# MetaSenseV02_2.net
KiCad netlist of a schematic drawn in EAGLE
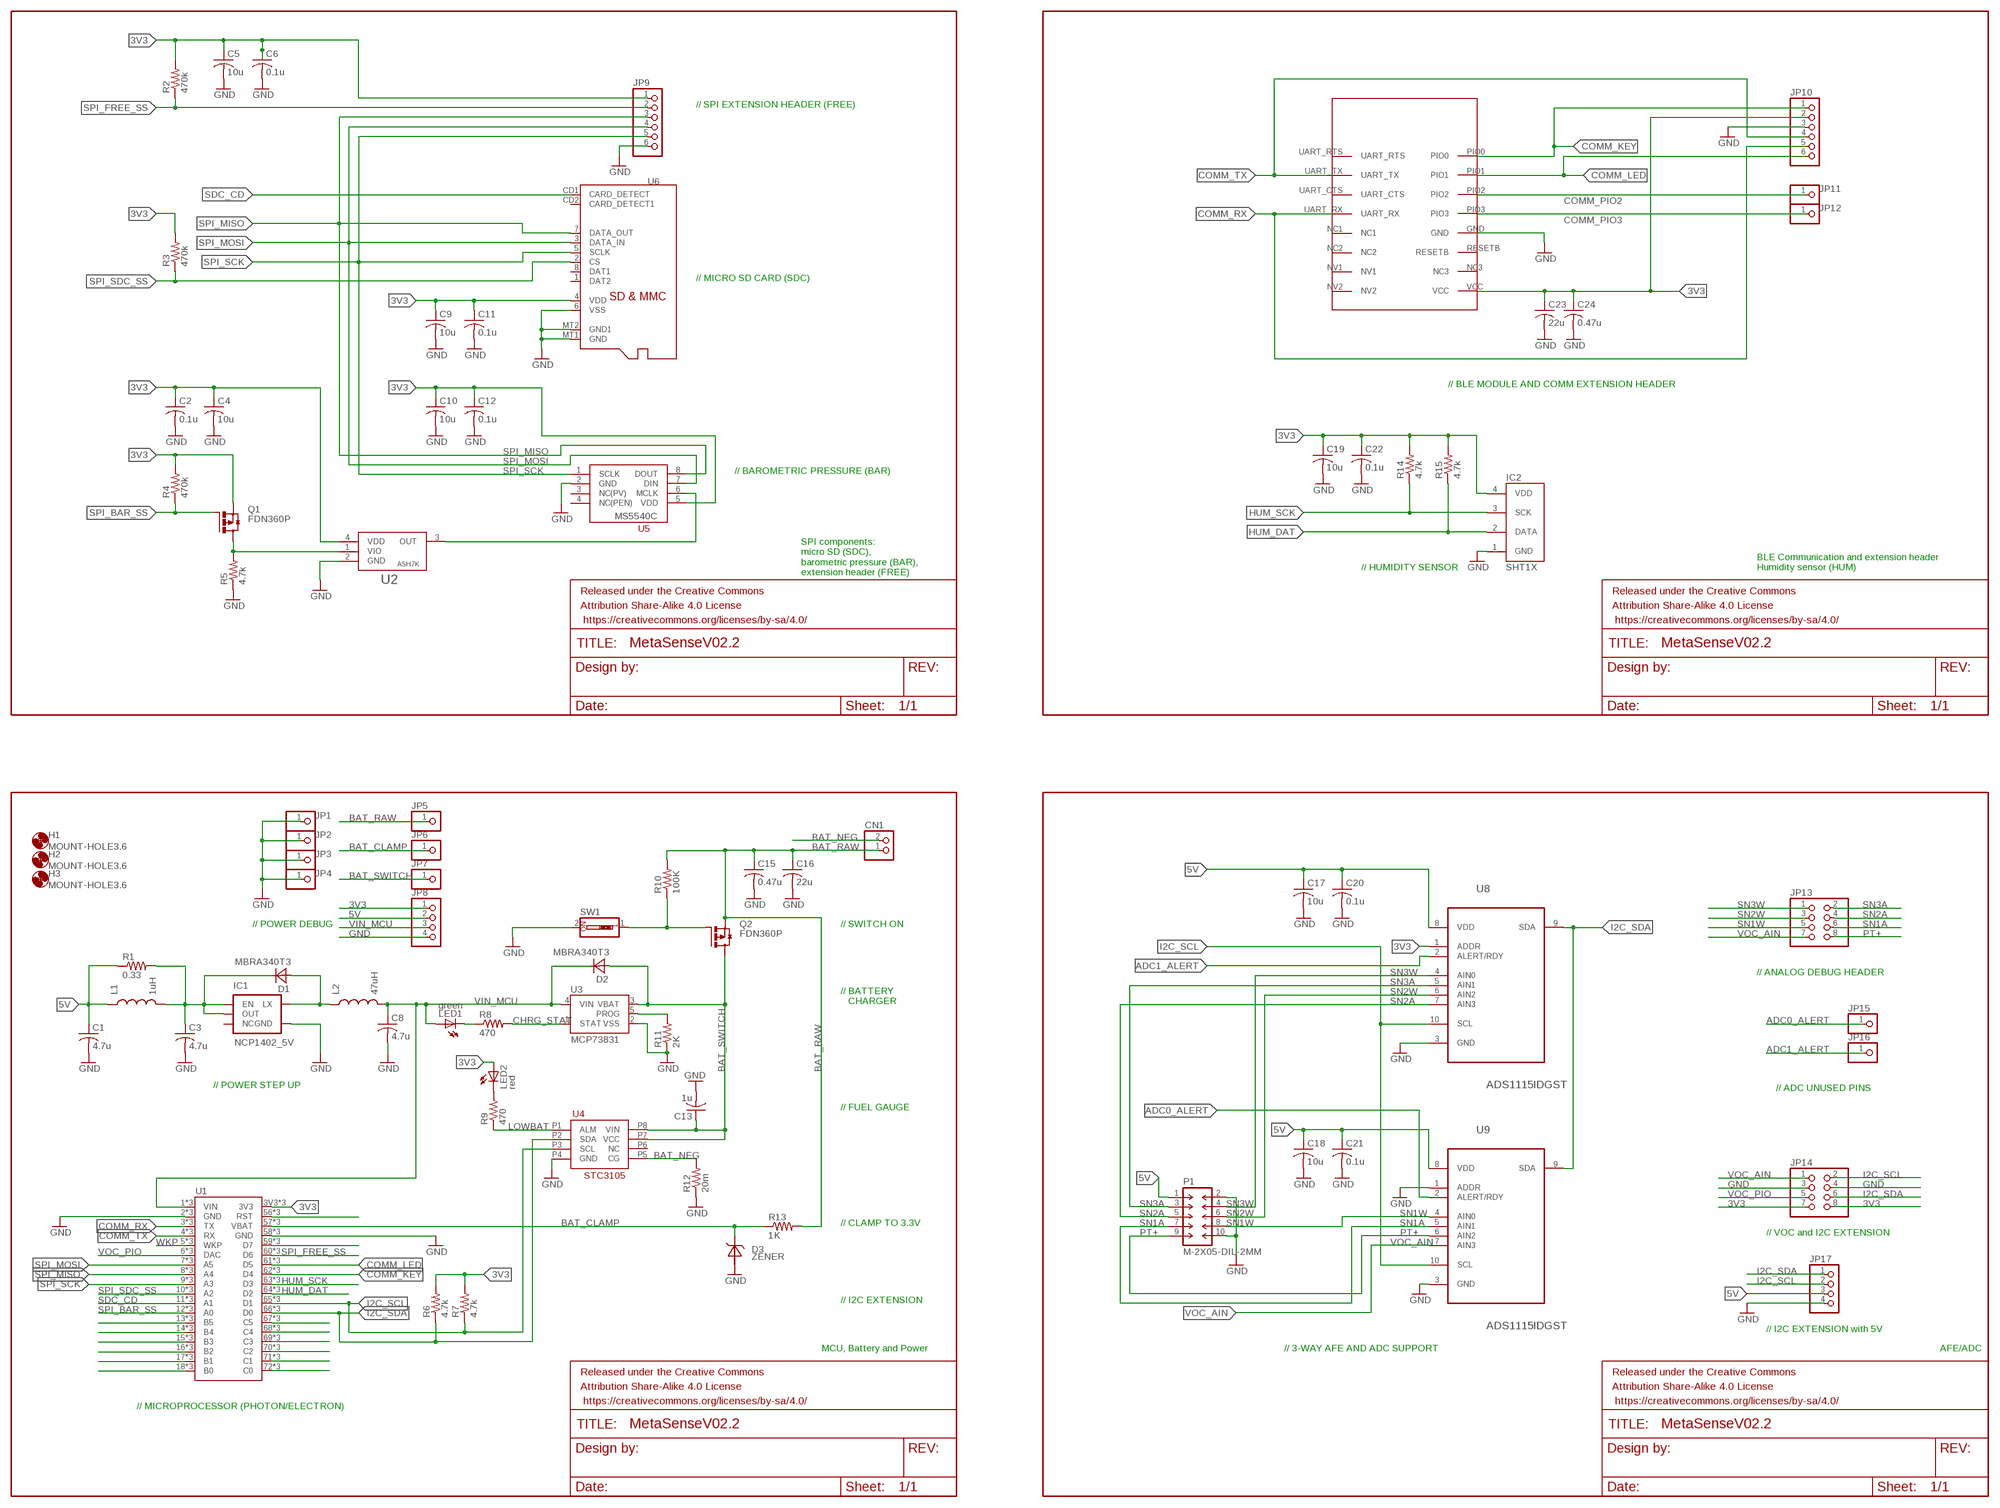
[diagram p0: schematic, sheet 1]

(export (version "E")
  (design (tool "Eeschema 10.0.6"))
  (components
    (comp (ref "C1")
      (value "4.7u")
      (footprint "eagle-import:C0805")
      (fields (field (name "MF") "VISHAY/DALE") (field (name "MPN") "IHLP2525CZER4R7M01"))
      (libsource (lib "eagle-import") (part "C-USC0805"))
    )
    (comp (ref "C2")
      (value "0.1u")
      (footprint "eagle-import:C0805")
      (fields (field (name "MF") "KEMET") (field (name "MPN") "C0603C102J5GACTU"))
      (libsource (lib "eagle-import") (part "C-USC0805"))
    )
    (comp (ref "C3")
      (value "4.7u")
      (footprint "eagle-import:C0805")
      (fields (field (name "MF") "VISHAY/DALE") (field (name "MPN") "IHLP2525CZER4R7M01"))
      (libsource (lib "eagle-import") (part "C-USC0805"))
    )
    (comp (ref "C4")
      (value "10u")
      (footprint "eagle-import:C0805")
      (fields (field (name "MPN") "C0805C106Z8VACTU"))
      (libsource (lib "eagle-import") (part "C-USC0805"))
    )
    (comp (ref "C5")
      (value "10u")
      (footprint "eagle-import:C0805")
      (fields (field (name "MPN") "C0805C106Z8VACTU"))
      (libsource (lib "eagle-import") (part "C-USC0805"))
    )
    (comp (ref "C6")
      (value "0.1u")
      (footprint "eagle-import:C0805")
      (fields (field (name "MF") "KEMET") (field (name "MPN") "C0603C102J5GACTU"))
      (libsource (lib "eagle-import") (part "C-USC0805"))
    )
    (comp (ref "C8")
      (value "4.7u")
      (footprint "eagle-import:C0805")
      (fields (field (name "MF") "VISHAY/DALE") (field (name "MPN") "IHLP2525CZER4R7M01"))
      (libsource (lib "eagle-import") (part "C-USC0805"))
    )
    (comp (ref "C9")
      (value "10u")
      (footprint "eagle-import:C0805")
      (fields (field (name "MPN") "C0805C106Z8VACTU"))
      (libsource (lib "eagle-import") (part "C-USC0805"))
    )
    (comp (ref "C10")
      (value "10u")
      (footprint "eagle-import:C0805")
      (fields (field (name "MPN") "C0805C106Z8VACTU"))
      (libsource (lib "eagle-import") (part "C-USC0805"))
    )
    (comp (ref "C11")
      (value "0.1u")
      (footprint "eagle-import:C0805")
      (fields (field (name "MF") "KEMET") (field (name "MPN") "C0603C102J5GACTU"))
      (libsource (lib "eagle-import") (part "C-USC0805"))
    )
    (comp (ref "C12")
      (value "0.1u")
      (footprint "eagle-import:C0805")
      (fields (field (name "MF") "KEMET") (field (name "MPN") "C0603C102J5GACTU"))
      (libsource (lib "eagle-import") (part "C-USC0805"))
    )
    (comp (ref "C13")
      (value "1u")
      (footprint "eagle-import:C0805")
      (fields (field (name "MF") "KEMET") (field (name "MPN") "C0402C471K5RACTU"))
      (libsource (lib "eagle-import") (part "C-USC0805"))
    )
    (comp (ref "C15")
      (value "0.47u")
      (footprint "eagle-import:C0805")
      (fields (field (name "MF") "KEMET") (field (name "MPN") "C0402C471K5RACTU"))
      (libsource (lib "eagle-import") (part "C-USC0805"))
    )
    (comp (ref "C16")
      (value "22u")
      (footprint "eagle-import:C0805")
      (libsource (lib "eagle-import") (part "C-USC0805"))
    )
    (comp (ref "C17")
      (value "10u")
      (footprint "eagle-import:C0805")
      (fields (field (name "MPN") "C0805C106Z8VACTU"))
      (libsource (lib "eagle-import") (part "C-USC0805"))
    )
    (comp (ref "C18")
      (value "10u")
      (footprint "eagle-import:C0805")
      (fields (field (name "MPN") "C0805C106Z8VACTU"))
      (libsource (lib "eagle-import") (part "C-USC0805"))
    )
    (comp (ref "C19")
      (value "10u")
      (footprint "eagle-import:C0805")
      (fields (field (name "MPN") "C0805C106Z8VACTU"))
      (libsource (lib "eagle-import") (part "C-USC0805"))
    )
    (comp (ref "C20")
      (value "0.1u")
      (footprint "eagle-import:C0805")
      (fields (field (name "MF") "KEMET") (field (name "MPN") "C0603C102J5GACTU"))
      (libsource (lib "eagle-import") (part "C-USC0805"))
    )
    (comp (ref "C21")
      (value "0.1u")
      (footprint "eagle-import:C0805")
      (fields (field (name "MF") "KEMET") (field (name "MPN") "C0603C102J5GACTU"))
      (libsource (lib "eagle-import") (part "C-USC0805"))
    )
    (comp (ref "C22")
      (value "0.1u")
      (footprint "eagle-import:C0805")
      (fields (field (name "MF") "KEMET") (field (name "MPN") "C0603C102J5GACTU"))
      (libsource (lib "eagle-import") (part "C-USC0805"))
    )
    (comp (ref "C23")
      (value "22u")
      (footprint "eagle-import:C0805")
      (libsource (lib "eagle-import") (part "C-USC0805"))
    )
    (comp (ref "C24")
      (value "0.47u")
      (footprint "eagle-import:C0805")
      (fields (field (name "MF") "KEMET") (field (name "MPN") "C0402C471K5RACTU"))
      (libsource (lib "eagle-import") (part "C-USC0805"))
    )
    (comp (ref "CN1")
      (value "JST_2PIN-THM")
      (footprint "eagle-import:JST-PH-2-THM")
      (libsource (lib "eagle-import") (part "JST_2PIN-THM"))
    )
    (comp (ref "D1")
      (value "MBRA340T3")
      (footprint "eagle-import:SMA")
      (libsource (lib "eagle-import") (part "MBRA340T3"))
    )
    (comp (ref "D2")
      (value "MBRA340T3")
      (footprint "eagle-import:SMA")
      (libsource (lib "eagle-import") (part "MBRA340T3"))
    )
    (comp (ref "D3")
      (value "ZENER")
      (footprint "eagle-import:SOD-123_MINI-SMA")
      (libsource (lib "eagle-import") (part "ZENER"))
    )
    (comp (ref "FRAME1")
      (value "FRAME-LETTERNO_PACKAGE")
      (footprint "eagle-import:DUMMY")
      (fields
        (field (name "DESIGNER") "Christine Chan")
        (field (name "VERSION") "v02")
        (field (name "OC_NEWARK") "unknown")
      )
      (libsource (lib "eagle-import") (part "FRAME-LETTERNO_PACKAGE"))
    )
    (comp (ref "FRAME2")
      (value "FRAME-LETTERNO_PACKAGE")
      (footprint "eagle-import:DUMMY")
      (fields
        (field (name "DESIGNER") "Christine Chan")
        (field (name "VERSION") "v02")
        (field (name "OC_NEWARK") "unknown")
      )
      (libsource (lib "eagle-import") (part "FRAME-LETTERNO_PACKAGE"))
    )
    (comp (ref "FRAME3")
      (value "FRAME-LETTERNO_PACKAGE")
      (footprint "eagle-import:DUMMY")
      (fields
        (field (name "DESIGNER") "Christine Chan")
        (field (name "OC_NEWARK") "unknown")
        (field (name "VERSION") "v02")
      )
      (libsource (lib "eagle-import") (part "FRAME-LETTERNO_PACKAGE"))
    )
    (comp (ref "FRAME4")
      (value "FRAME-LETTERNO_PACKAGE")
      (footprint "eagle-import:DUMMY")
      (fields
        (field (name "DESIGNER") "Christine Chan")
        (field (name "OC_NEWARK") "unknown")
        (field (name "VERSION") "v02")
      )
      (libsource (lib "eagle-import") (part "FRAME-LETTERNO_PACKAGE"))
    )
    (comp (ref "H1")
      (value "MOUNT-HOLE3.6")
      (footprint "eagle-import:3,6")
      (libsource (lib "eagle-import") (part "MOUNT-HOLE3.6"))
    )
    (comp (ref "H2")
      (value "MOUNT-HOLE3.6")
      (footprint "eagle-import:3,6")
      (libsource (lib "eagle-import") (part "MOUNT-HOLE3.6"))
    )
    (comp (ref "H3")
      (value "MOUNT-HOLE3.6")
      (footprint "eagle-import:3,6")
      (libsource (lib "eagle-import") (part "MOUNT-HOLE3.6"))
    )
    (comp (ref "IC1")
      (value "NCP1402_5V")
      (footprint "eagle-import:SOT23-5")
      (fields (field (name "MF") "ON SEMICONDUCTOR") (field (name "MPN") "NCP1402SN50T1G"))
      (libsource (lib "eagle-import") (part "V_REG_NCP1400_5V"))
    )
    (comp (ref "IC2")
      (value "SHT1X")
      (footprint "eagle-import:SHT1X")
      (fields (field (name "MF") "SENSIRION AG") (field (name "MPN") "SHT11"))
      (libsource (lib "eagle-import") (part "SHT1X"))
    )
    (comp (ref "JP1")
      (value "PINHD-1X1")
      (footprint "eagle-import:1X01")
      (libsource (lib "eagle-import") (part "pinhead_PINHD-1X1"))
    )
    (comp (ref "JP2")
      (value "PINHD-1X1")
      (footprint "eagle-import:1X01")
      (libsource (lib "eagle-import") (part "pinhead_PINHD-1X1"))
    )
    (comp (ref "JP3")
      (value "PINHD-1X1")
      (footprint "eagle-import:1X01")
      (libsource (lib "eagle-import") (part "pinhead_PINHD-1X1"))
    )
    (comp (ref "JP4")
      (value "PINHD-1X1")
      (footprint "eagle-import:1X01")
      (libsource (lib "eagle-import") (part "pinhead_PINHD-1X1"))
    )
    (comp (ref "JP5")
      (value "PINHD-1X1")
      (footprint "eagle-import:1X01")
      (libsource (lib "eagle-import") (part "pinhead_PINHD-1X1"))
    )
    (comp (ref "JP6")
      (value "PINHD-1X1")
      (footprint "eagle-import:1X01")
      (libsource (lib "eagle-import") (part "pinhead_PINHD-1X1"))
    )
    (comp (ref "JP7")
      (value "PINHD-1X1")
      (footprint "eagle-import:1X01")
      (libsource (lib "eagle-import") (part "pinhead_PINHD-1X1"))
    )
    (comp (ref "JP8")
      (value "PINHD-1X4")
      (footprint "eagle-import:1X04")
      (libsource (lib "eagle-import") (part "PINHD-1X4"))
    )
    (comp (ref "JP9")
      (value "PINHD-1X6")
      (footprint "eagle-import:1X06")
      (libsource (lib "eagle-import") (part "PINHD-1X6"))
    )
    (comp (ref "JP10")
      (value "PINHD-1X6")
      (footprint "eagle-import:1X06")
      (libsource (lib "eagle-import") (part "PINHD-1X6"))
    )
    (comp (ref "JP11")
      (value "PINHD-1X1")
      (footprint "eagle-import:1X01")
      (libsource (lib "eagle-import") (part "pinhead_PINHD-1X1"))
    )
    (comp (ref "JP12")
      (value "PINHD-1X1")
      (footprint "eagle-import:1X01")
      (libsource (lib "eagle-import") (part "pinhead_PINHD-1X1"))
    )
    (comp (ref "JP13")
      (value "PINHD-2X4")
      (footprint "eagle-import:2X04")
      (libsource (lib "eagle-import") (part "PINHD-2X4"))
    )
    (comp (ref "JP14")
      (value "PINHD-2X4")
      (footprint "eagle-import:2X04")
      (libsource (lib "eagle-import") (part "PINHD-2X4"))
    )
    (comp (ref "JP15")
      (value "PINHD-1X1")
      (footprint "eagle-import:1X01")
      (libsource (lib "eagle-import") (part "PINHD-1X1"))
    )
    (comp (ref "JP16")
      (value "PINHD-1X1")
      (footprint "eagle-import:1X01")
      (libsource (lib "eagle-import") (part "PINHD-1X1"))
    )
    (comp (ref "JP17")
      (value "PINHD-1X4")
      (footprint "eagle-import:1X04")
      (libsource (lib "eagle-import") (part "PINHD-1X4"))
    )
    (comp (ref "L1")
      (value "1uH")
      (footprint "eagle-import:0805")
      (fields (field (name "MPN") "LQM21NN1R0K10D"))
      (libsource (lib "eagle-import") (part "INDUCTOR0805"))
    )
    (comp (ref "L2")
      (value "47uH")
      (footprint "eagle-import:0805")
      (libsource (lib "eagle-import") (part "INDUCTOR0805"))
    )
    (comp (ref "LED1")
      (value "green")
      (footprint "eagle-import:CHIPLED_0805")
      (fields (field (name "MPN") "NTE30003"))
      (libsource (lib "eagle-import") (part "LEDCHIPLED_0805"))
    )
    (comp (ref "LED2")
      (value "red")
      (footprint "eagle-import:CHIPLED_0805")
      (fields (field (name "MPN") "NTE30002"))
      (libsource (lib "eagle-import") (part "LEDCHIPLED_0805"))
    )
    (comp (ref "P1")
      (value "M-2X05-DIL-2MM")
      (footprint "eagle-import:DIL-2MM-2X05")
      (libsource (lib "eagle-import") (part "M-2X05-DIL-2MM"))
    )
    (comp (ref "Q1")
      (value "FDN360P")
      (footprint "eagle-import:SUPER-SOT3")
      (fields (field (name "MF") "FAIRCHILD SEMICONDUCTOR"))
      (libsource (lib "eagle-import") (part "FDN360P"))
    )
    (comp (ref "Q2")
      (value "FDN360P")
      (footprint "eagle-import:SUPER-SOT3")
      (fields (field (name "MF") "FAIRCHILD SEMICONDUCTOR"))
      (libsource (lib "eagle-import") (part "FDN360P"))
    )
    (comp (ref "R1")
      (value "0.33")
      (footprint "eagle-import:R0805")
      (libsource (lib "eagle-import") (part "R-US_R0805"))
    )
    (comp (ref "R2")
      (value "470k")
      (footprint "eagle-import:R0805")
      (fields (field (name "MF") "VISHAY/DALE") (field (name "MPN") "CRCW0805470KJNEA"))
      (libsource (lib "eagle-import") (part "R-US_R0805"))
    )
    (comp (ref "R3")
      (value "470k")
      (footprint "eagle-import:R0805")
      (fields (field (name "MF") "VISHAY/DALE") (field (name "MPN") "CRCW0805470KJNEA"))
      (libsource (lib "eagle-import") (part "R-US_R0805"))
    )
    (comp (ref "R4")
      (value "470k")
      (footprint "eagle-import:R0805")
      (fields (field (name "MF") "VISHAY/DALE") (field (name "MPN") "CRCW0805470KJNEA"))
      (libsource (lib "eagle-import") (part "R-US_R0805"))
    )
    (comp (ref "R5")
      (value "4.7k")
      (footprint "eagle-import:R0805")
      (fields (field (name "MF") "VISHAY/DALE") (field (name "MPN") "CRCW08054K70JNEA"))
      (libsource (lib "eagle-import") (part "R-US_R0805"))
    )
    (comp (ref "R6")
      (value "4.7k")
      (footprint "eagle-import:R0805")
      (fields (field (name "MF") "VISHAY/DALE") (field (name "MPN") "CRCW08054K70JNEA"))
      (libsource (lib "eagle-import") (part "R-US_R0805"))
    )
    (comp (ref "R7")
      (value "4.7k")
      (footprint "eagle-import:R0805")
      (fields (field (name "MF") "VISHAY/DALE") (field (name "MPN") "CRCW08054K70JNEA"))
      (libsource (lib "eagle-import") (part "R-US_R0805"))
    )
    (comp (ref "R8")
      (value "470")
      (footprint "eagle-import:R0805")
      (libsource (lib "eagle-import") (part "R-US_R0805"))
    )
    (comp (ref "R9")
      (value "470")
      (footprint "eagle-import:R0805")
      (libsource (lib "eagle-import") (part "R-US_R0805"))
    )
    (comp (ref "R10")
      (value "100K")
      (footprint "eagle-import:R0805")
      (fields (field (name "MPN") "ERA-6AEB104V"))
      (libsource (lib "eagle-import") (part "R-US_R0805"))
    )
    (comp (ref "R11")
      (value "2K")
      (footprint "eagle-import:R0805")
      (libsource (lib "eagle-import") (part "R-US_R0805"))
    )
    (comp (ref "R12")
      (value "20m")
      (footprint "eagle-import:R0805")
      (libsource (lib "eagle-import") (part "R-US_R0805"))
    )
    (comp (ref "R13")
      (value "1K")
      (footprint "eagle-import:R0805")
      (fields (field (name "MPN") "ERJ-6ENF1001V"))
      (libsource (lib "eagle-import") (part "R-US_R0805"))
    )
    (comp (ref "R14")
      (value "4.7k")
      (footprint "eagle-import:R0805")
      (fields (field (name "MF") "VISHAY/DALE") (field (name "MPN") "CRCW08054K70JNEA"))
      (libsource (lib "eagle-import") (part "R-US_R0805"))
    )
    (comp (ref "R15")
      (value "4.7k")
      (footprint "eagle-import:R0805")
      (fields (field (name "MF") "VISHAY/DALE") (field (name "MPN") "CRCW08054K70JNEA"))
      (libsource (lib "eagle-import") (part "R-US_R0805"))
    )
    (comp (ref "SW1")
      (value "SW_DIP-1")
      (footprint "eagle-import:EDG-01")
      (libsource (lib "eagle-import") (part "SW_DIP-1"))
    )
    (comp (ref "U1")
      (value "ELECTRONDUALROW")
      (footprint "eagle-import:ELECTRON_DUAL-ROW")
      (libsource (lib "eagle-import") (part "ELECTRONDUALROW"))
    )
    (comp (ref "U2")
      (value "ASH7K-OSCILLATOR")
      (footprint "eagle-import:SMD-4PAD")
      (libsource (lib "eagle-import") (part "ASH7K-OSCILLATOR"))
    )
    (comp (ref "U3")
      (value "MCP73831")
      (footprint "eagle-import:SOT23-5")
      (fields (field (name "MPN") "MCP73831T-2DCI/OT"))
      (libsource (lib "eagle-import") (part "MCP73831"))
    )
    (comp (ref "U4")
      (value "STC3105")
      (footprint "eagle-import:TDFN-8-3X2MM")
      (libsource (lib "eagle-import") (part "STC3105"))
    )
    (comp (ref "U5")
      (value "MS5540CSMD")
      (footprint "eagle-import:SMD-HYBRID")
      (libsource (lib "eagle-import") (part "MS5540CSMD"))
    )
    (comp (ref "U6")
      (value "MICROSD")
      (footprint "eagle-import:MICROSD")
      (fields (field (name "MPN") "2908-05WB-MG"))
      (libsource (lib "eagle-import") (part "MICROSD"))
    )
    (comp (ref "U7")
      (value "HM-11")
      (footprint "eagle-import:HM-11")
      (libsource (lib "eagle-import") (part "HM-11"))
    )
    (comp (ref "U8")
      (value "ADS1115IDGST")
      (footprint "eagle-import:SOP50P490X110-10N")
      (libsource (lib "eagle-import") (part "ADS1115IDGST"))
    )
    (comp (ref "U9")
      (value "ADS1115IDGST")
      (footprint "eagle-import:SOP50P490X110-10N")
      (libsource (lib "eagle-import") (part "ADS1115IDGST"))
    )
  )
  (nets
    (net (code "1") (name "/BAT_CLAMP") (class "Default")
      (node (ref "D3") (pin "C") (pinfunction "CAT_C") (pintype "bidirectional"))
      (node (ref "JP6") (pin "1") (pinfunction "1_1") (pintype "passive"))
      (node (ref "R13") (pin "1") (pinfunction "1_1") (pintype "passive"))
      (node (ref "U1") (pin "57") (pinfunction "VBAT_57") (pintype "passive"))
      (node (ref "U1") (pin "93") (pinfunction "VBAT_93") (pintype "passive"))
      (node (ref "U1") (pin "VBAT") (pinfunction "VBAT_VBAT") (pintype "passive"))
    )
    (net (code "2") (name "/BAT_NEG") (class "Default")
      (node (ref "CN1") (pin "2") (pinfunction "1_2") (pintype "passive"))
      (node (ref "R12") (pin "2") (pinfunction "2_2") (pintype "passive"))
      (node (ref "U4") (pin "P5") (pinfunction "CG_P5") (pintype "bidirectional"))
    )
    (net (code "3") (name "/BAT_RAW") (class "Default")
      (node (ref "C15") (pin "1") (pinfunction "1_1") (pintype "passive"))
      (node (ref "C16") (pin "1") (pinfunction "1_1") (pintype "passive"))
      (node (ref "CN1") (pin "1") (pinfunction "2_1") (pintype "passive"))
      (node (ref "JP5") (pin "1") (pinfunction "1_1") (pintype "passive"))
      (node (ref "Q2") (pin "2") (pinfunction "S_2") (pintype "passive"))
      (node (ref "R10") (pin "2") (pinfunction "2_2") (pintype "passive"))
      (node (ref "R13") (pin "2") (pinfunction "2_2") (pintype "passive"))
    )
    (net (code "4") (name "/BAT_SWITCH") (class "Default")
      (node (ref "C13") (pin "1") (pinfunction "1_1") (pintype "passive"))
      (node (ref "D2") (pin "A") (pinfunction "A_A") (pintype "passive"))
      (node (ref "JP7") (pin "1") (pinfunction "1_1") (pintype "passive"))
      (node (ref "Q2") (pin "3") (pinfunction "D_3") (pintype "passive"))
      (node (ref "U3") (pin "3") (pinfunction "VBAT_3") (pintype "power_in"))
      (node (ref "U4") (pin "P7") (pinfunction "VCC_P7") (pintype "bidirectional"))
      (node (ref "U4") (pin "P8") (pinfunction "VIN_P8") (pintype "bidirectional"))
    )
    (net (code "5") (name "/CHRG_STAT") (class "Default")
      (node (ref "R8") (pin "2") (pinfunction "2_2") (pintype "passive"))
      (node (ref "U3") (pin "1") (pinfunction "STAT_1") (pintype "output"))
    )
    (net (code "6") (name "/COMM_PIO2") (class "Default")
      (node (ref "JP11") (pin "1") (pinfunction "1_1") (pintype "passive"))
      (node (ref "U7") (pin "PIO2") (pinfunction "PIO2_PIO2") (pintype "bidirectional"))
    )
    (net (code "7") (name "/COMM_PIO3") (class "Default")
      (node (ref "JP12") (pin "1") (pinfunction "1_1") (pintype "passive"))
      (node (ref "U7") (pin "PIO3") (pinfunction "PIO3_PIO3") (pintype "bidirectional"))
    )
    (net (code "8") (name "/LOWBAT") (class "Default")
      (node (ref "R9") (pin "1") (pinfunction "1_1") (pintype "passive"))
      (node (ref "U4") (pin "P1") (pinfunction "ALM_P1") (pintype "bidirectional"))
    )
    (net (code "9") (name "/PT+") (class "Default")
      (node (ref "JP13") (pin "8") (pinfunction "8_8") (pintype "passive"))
      (node (ref "P1") (pin "9") (pinfunction "9_9") (pintype "passive"))
      (node (ref "U9") (pin "6") (pinfunction "AIN2_6") (pintype "input"))
    )
    (net (code "10") (name "/SN1A") (class "Default")
      (node (ref "JP13") (pin "6") (pinfunction "6_6") (pintype "passive"))
      (node (ref "P1") (pin "7") (pinfunction "7_7") (pintype "passive"))
      (node (ref "U9") (pin "5") (pinfunction "AIN1_5") (pintype "input"))
    )
    (net (code "11") (name "/SN1W") (class "Default")
      (node (ref "JP13") (pin "5") (pinfunction "5_5") (pintype "passive"))
      (node (ref "P1") (pin "8") (pinfunction "8_8") (pintype "passive"))
      (node (ref "U9") (pin "4") (pinfunction "AIN0_4") (pintype "input"))
    )
    (net (code "12") (name "/SN2A") (class "Default")
      (node (ref "JP13") (pin "4") (pinfunction "4_4") (pintype "passive"))
      (node (ref "P1") (pin "5") (pinfunction "5_5") (pintype "passive"))
      (node (ref "U8") (pin "7") (pinfunction "AIN3_7") (pintype "input"))
    )
    (net (code "13") (name "/SN2W") (class "Default")
      (node (ref "JP13") (pin "3") (pinfunction "3_3") (pintype "passive"))
      (node (ref "P1") (pin "6") (pinfunction "6_6") (pintype "passive"))
      (node (ref "U8") (pin "6") (pinfunction "AIN2_6") (pintype "input"))
    )
    (net (code "14") (name "/SN3A") (class "Default")
      (node (ref "JP13") (pin "2") (pinfunction "2_2") (pintype "passive"))
      (node (ref "P1") (pin "3") (pinfunction "3_3") (pintype "passive"))
      (node (ref "U8") (pin "5") (pinfunction "AIN1_5") (pintype "input"))
    )
    (net (code "15") (name "/SN3W") (class "Default")
      (node (ref "JP13") (pin "1") (pinfunction "1_1") (pintype "passive"))
      (node (ref "P1") (pin "4") (pinfunction "4_4") (pintype "passive"))
      (node (ref "U8") (pin "4") (pinfunction "AIN0_4") (pintype "input"))
    )
    (net (code "16") (name "/VIN_MCU") (class "Default")
      (node (ref "C8") (pin "1") (pinfunction "1_1") (pintype "passive"))
      (node (ref "D2") (pin "C") (pinfunction "C_C") (pintype "passive"))
      (node (ref "JP8") (pin "3") (pinfunction "3_3") (pintype "passive"))
      (node (ref "L2") (pin "2") (pinfunction "2_2") (pintype "passive"))
      (node (ref "LED1") (pin "A") (pinfunction "A_A") (pintype "passive"))
      (node (ref "U1") (pin "1") (pinfunction "VIN_1") (pintype "power_in"))
      (node (ref "U1") (pin "37") (pinfunction "VIN_37") (pintype "power_in"))
      (node (ref "U1") (pin "VIN") (pinfunction "VIN_VIN") (pintype "power_in"))
      (node (ref "U3") (pin "4") (pinfunction "VIN_4") (pintype "power_in"))
    )
    (net (code "17") (name "/VOC_PIO") (class "Default")
      (node (ref "JP14") (pin "5") (pinfunction "5_5") (pintype "passive"))
      (node (ref "U1") (pin "42") (pinfunction "DAC_42") (pintype "bidirectional"))
      (node (ref "U1") (pin "6") (pinfunction "DAC_6") (pintype "bidirectional"))
      (node (ref "U1") (pin "DAC") (pinfunction "DAC_DAC") (pintype "bidirectional"))
    )
    (net (code "18") (name "/WKP") (class "Default")
      (node (ref "U1") (pin "41") (pinfunction "WKP_41") (pintype "bidirectional"))
      (node (ref "U1") (pin "5") (pinfunction "WKP_5") (pintype "bidirectional"))
      (node (ref "U1") (pin "WKP") (pinfunction "WKP_WKP") (pintype "bidirectional"))
    )
    (net (code "19") (name "3V3") (class "Default")
      (node (ref "C10") (pin "1") (pinfunction "1_1") (pintype "passive"))
      (node (ref "C11") (pin "1") (pinfunction "1_1") (pintype "passive"))
      (node (ref "C12") (pin "1") (pinfunction "1_1") (pintype "passive"))
      (node (ref "C19") (pin "1") (pinfunction "1_1") (pintype "passive"))
      (node (ref "C2") (pin "1") (pinfunction "1_1") (pintype "passive"))
      (node (ref "C22") (pin "1") (pinfunction "1_1") (pintype "passive"))
      (node (ref "C23") (pin "1") (pinfunction "1_1") (pintype "passive"))
      (node (ref "C24") (pin "1") (pinfunction "1_1") (pintype "passive"))
      (node (ref "C4") (pin "1") (pinfunction "1_1") (pintype "passive"))
      (node (ref "C5") (pin "1") (pinfunction "1_1") (pintype "passive"))
      (node (ref "C6") (pin "1") (pinfunction "1_1") (pintype "passive"))
      (node (ref "C9") (pin "1") (pinfunction "1_1") (pintype "passive"))
      (node (ref "IC2") (pin "4") (pinfunction "VDD_4") (pintype "power_in"))
      (node (ref "JP10") (pin "2") (pinfunction "2_2") (pintype "passive"))
      (node (ref "JP14") (pin "7") (pinfunction "7_7") (pintype "passive"))
      (node (ref "JP14") (pin "8") (pinfunction "8_8") (pintype "passive"))
      (node (ref "JP8") (pin "1") (pinfunction "1_1") (pintype "passive"))
      (node (ref "JP9") (pin "1") (pinfunction "1_1") (pintype "passive"))
      (node (ref "LED2") (pin "A") (pinfunction "A_A") (pintype "passive"))
      (node (ref "Q1") (pin "2") (pinfunction "S_2") (pintype "passive"))
      (node (ref "R14") (pin "2") (pinfunction "2_2") (pintype "passive"))
      (node (ref "R15") (pin "2") (pinfunction "2_2") (pintype "passive"))
      (node (ref "R2") (pin "2") (pinfunction "2_2") (pintype "passive"))
      (node (ref "R3") (pin "2") (pinfunction "2_2") (pintype "passive"))
      (node (ref "R4") (pin "2") (pinfunction "2_2") (pintype "passive"))
      (node (ref "R6") (pin "2") (pinfunction "2_2") (pintype "passive"))
      (node (ref "R7") (pin "2") (pinfunction "2_2") (pintype "passive"))
      (node (ref "U1") (pin "3V3") (pinfunction "3V3_3V3") (pintype "power_in"))
      (node (ref "U1") (pin "55") (pinfunction "3V3_55") (pintype "power_in"))
      (node (ref "U1") (pin "91") (pinfunction "3V3_91") (pintype "power_in"))
      (node (ref "U2") (pin "4") (pinfunction "VDD_4") (pintype "bidirectional"))
      (node (ref "U5") (pin "5") (pinfunction "VDD_5") (pintype "bidirectional"))
      (node (ref "U6") (pin "4") (pinfunction "VDD_4") (pintype "power_in"))
      (node (ref "U7") (pin "VCC") (pinfunction "VCC_VCC") (pintype "bidirectional"))
      (node (ref "U8") (pin "1") (pinfunction "ADDR_1") (pintype "input"))
    )
    (net (code "20") (name "5V") (class "Default")
      (node (ref "C1") (pin "1") (pinfunction "1_1") (pintype "passive"))
      (node (ref "C17") (pin "1") (pinfunction "1_1") (pintype "passive"))
      (node (ref "C18") (pin "1") (pinfunction "1_1") (pintype "passive"))
      (node (ref "C20") (pin "1") (pinfunction "1_1") (pintype "passive"))
      (node (ref "C21") (pin "1") (pinfunction "1_1") (pintype "passive"))
      (node (ref "JP17") (pin "3") (pinfunction "3_3") (pintype "passive"))
      (node (ref "JP8") (pin "2") (pinfunction "2_2") (pintype "passive"))
      (node (ref "L1") (pin "1") (pinfunction "1_1") (pintype "passive"))
      (node (ref "P1") (pin "1") (pinfunction "1_1") (pintype "passive"))
      (node (ref "R1") (pin "1") (pinfunction "1_1") (pintype "passive"))
      (node (ref "U8") (pin "8") (pinfunction "VDD_8") (pintype "power_in"))
      (node (ref "U9") (pin "8") (pinfunction "VDD_8") (pintype "power_in"))
    )
    (net (code "21") (name "ADC0_ALERT") (class "Default")
      (node (ref "JP15") (pin "1") (pinfunction "1_1") (pintype "passive"))
      (node (ref "U9") (pin "2") (pinfunction "ALERT/RDY_2") (pintype "input"))
    )
    (net (code "22") (name "ADC1_ALERT") (class "Default")
      (node (ref "JP16") (pin "1") (pinfunction "1_1") (pintype "passive"))
      (node (ref "U8") (pin "2") (pinfunction "ALERT/RDY_2") (pintype "input"))
    )
    (net (code "23") (name "COMM_KEY") (class "Default")
      (node (ref "JP10") (pin "1") (pinfunction "1_1") (pintype "passive"))
      (node (ref "U1") (pin "62") (pinfunction "D4_62") (pintype "bidirectional"))
      (node (ref "U1") (pin "98") (pinfunction "D4_98") (pintype "bidirectional"))
      (node (ref "U1") (pin "D4") (pinfunction "D4_D4") (pintype "bidirectional"))
      (node (ref "U7") (pin "PIO0") (pinfunction "PIO0_PIO0") (pintype "bidirectional"))
    )
    (net (code "24") (name "COMM_LED") (class "Default")
      (node (ref "JP10") (pin "6") (pinfunction "6_6") (pintype "passive"))
      (node (ref "U1") (pin "61") (pinfunction "D5_61") (pintype "bidirectional"))
      (node (ref "U1") (pin "97") (pinfunction "D5_97") (pintype "bidirectional"))
      (node (ref "U1") (pin "D5") (pinfunction "D5_D5") (pintype "bidirectional"))
      (node (ref "U7") (pin "PIO1") (pinfunction "PIO1_PIO1") (pintype "bidirectional"))
    )
    (net (code "25") (name "COMM_RX") (class "Default")
      (node (ref "JP10") (pin "5") (pinfunction "5_5") (pintype "passive"))
      (node (ref "U1") (pin "3") (pinfunction "TX_3") (pintype "bidirectional"))
      (node (ref "U1") (pin "39") (pinfunction "TX_39") (pintype "bidirectional"))
      (node (ref "U1") (pin "TX") (pinfunction "TX_TX") (pintype "bidirectional"))
      (node (ref "U7") (pin "UART_RX") (pinfunction "UART_RX_UART_RX") (pintype "bidirectional"))
    )
    (net (code "26") (name "COMM_TX") (class "Default")
      (node (ref "JP10") (pin "4") (pinfunction "4_4") (pintype "passive"))
      (node (ref "U1") (pin "4") (pinfunction "RX_4") (pintype "bidirectional"))
      (node (ref "U1") (pin "40") (pinfunction "RX_40") (pintype "bidirectional"))
      (node (ref "U1") (pin "RX") (pinfunction "RX_RX") (pintype "bidirectional"))
      (node (ref "U7") (pin "UART_TX") (pinfunction "UART_TX_UART_TX") (pintype "bidirectional"))
    )
    (net (code "27") (name "GND") (class "Default")
      (node (ref "C1") (pin "2") (pinfunction "2_2") (pintype "passive"))
      (node (ref "C10") (pin "2") (pinfunction "2_2") (pintype "passive"))
      (node (ref "C11") (pin "2") (pinfunction "2_2") (pintype "passive"))
      (node (ref "C12") (pin "2") (pinfunction "2_2") (pintype "passive"))
      (node (ref "C13") (pin "2") (pinfunction "2_2") (pintype "passive"))
      (node (ref "C15") (pin "2") (pinfunction "2_2") (pintype "passive"))
      (node (ref "C16") (pin "2") (pinfunction "2_2") (pintype "passive"))
      (node (ref "C17") (pin "2") (pinfunction "2_2") (pintype "passive"))
      (node (ref "C18") (pin "2") (pinfunction "2_2") (pintype "passive"))
      (node (ref "C19") (pin "2") (pinfunction "2_2") (pintype "passive"))
      (node (ref "C2") (pin "2") (pinfunction "2_2") (pintype "passive"))
      (node (ref "C20") (pin "2") (pinfunction "2_2") (pintype "passive"))
      (node (ref "C21") (pin "2") (pinfunction "2_2") (pintype "passive"))
      (node (ref "C22") (pin "2") (pinfunction "2_2") (pintype "passive"))
      (node (ref "C23") (pin "2") (pinfunction "2_2") (pintype "passive"))
      (node (ref "C24") (pin "2") (pinfunction "2_2") (pintype "passive"))
      (node (ref "C3") (pin "2") (pinfunction "2_2") (pintype "passive"))
      (node (ref "C4") (pin "2") (pinfunction "2_2") (pintype "passive"))
      (node (ref "C5") (pin "2") (pinfunction "2_2") (pintype "passive"))
      (node (ref "C6") (pin "2") (pinfunction "2_2") (pintype "passive"))
      (node (ref "C8") (pin "2") (pinfunction "2_2") (pintype "passive"))
      (node (ref "C9") (pin "2") (pinfunction "2_2") (pintype "passive"))
      (node (ref "D3") (pin "A") (pinfunction "AN_A") (pintype "bidirectional"))
      (node (ref "IC1") (pin "4") (pinfunction "GND_4") (pintype "input"))
      (node (ref "IC2") (pin "1") (pinfunction "GND_1") (pintype "power_in"))
      (node (ref "JP1") (pin "1") (pinfunction "1_1") (pintype "passive"))
      (node (ref "JP10") (pin "3") (pinfunction "3_3") (pintype "passive"))
      (node (ref "JP14") (pin "3") (pinfunction "3_3") (pintype "passive"))
      (node (ref "JP14") (pin "4") (pinfunction "4_4") (pintype "passive"))
      (node (ref "JP17") (pin "4") (pinfunction "4_4") (pintype "passive"))
      (node (ref "JP2") (pin "1") (pinfunction "1_1") (pintype "passive"))
      (node (ref "JP3") (pin "1") (pinfunction "1_1") (pintype "passive"))
      (node (ref "JP4") (pin "1") (pinfunction "1_1") (pintype "passive"))
      (node (ref "JP8") (pin "4") (pinfunction "4_4") (pintype "passive"))
      (node (ref "JP9") (pin "6") (pinfunction "6_6") (pintype "passive"))
      (node (ref "P1") (pin "10") (pinfunction "10_10") (pintype "passive"))
      (node (ref "P1") (pin "2") (pinfunction "2_2") (pintype "passive"))
      (node (ref "R11") (pin "1") (pinfunction "1_1") (pintype "passive"))
      (node (ref "R12") (pin "1") (pinfunction "1_1") (pintype "passive"))
      (node (ref "R5") (pin "1") (pinfunction "1_1") (pintype "passive"))
      (node (ref "SW1") (pin "2") (pinfunction "2_2") (pintype "passive"))
      (node (ref "U1") (pin "2") (pinfunction "GND_2") (pintype "power_in"))
      (node (ref "U1") (pin "38") (pinfunction "GND_38") (pintype "power_in"))
      (node (ref "U1") (pin "58") (pinfunction "GND_58") (pintype "power_in"))
      (node (ref "U1") (pin "94") (pinfunction "GND_94") (pintype "power_in"))
      (node (ref "U1") (pin "GND") (pinfunction "GND_GND") (pintype "power_in"))
      (node (ref "U1") (pin "GND@2") (pinfunction "GND_GND@2") (pintype "power_in"))
      (node (ref "U2") (pin "2") (pinfunction "GND_2") (pintype "bidirectional"))
      (node (ref "U3") (pin "2") (pinfunction "VSS_2") (pintype "power_in"))
      (node (ref "U4") (pin "P4") (pinfunction "GND_P4") (pintype "bidirectional"))
      (node (ref "U5") (pin "2") (pinfunction "GND_2") (pintype "bidirectional"))
      (node (ref "U6") (pin "6") (pinfunction "VSS_6") (pintype "power_in"))
      (node (ref "U6") (pin "MT1") (pinfunction "GND_MT1") (pintype "power_in"))
      (node (ref "U6") (pin "MT2") (pinfunction "GND1_MT2") (pintype "power_in"))
      (node (ref "U7") (pin "GND") (pinfunction "GND_GND") (pintype "bidirectional"))
      (node (ref "U8") (pin "3") (pinfunction "GND_3") (pintype "passive"))
      (node (ref "U9") (pin "1") (pinfunction "ADDR_1") (pintype "input"))
      (node (ref "U9") (pin "3") (pinfunction "GND_3") (pintype "passive"))
    )
    (net (code "28") (name "HUM_DAT") (class "Default")
      (node (ref "IC2") (pin "2") (pinfunction "DATA_2") (pintype "open_collector"))
      (node (ref "R15") (pin "1") (pinfunction "1_1") (pintype "passive"))
      (node (ref "U1") (pin "100") (pinfunction "D2_100") (pintype "bidirectional"))
      (node (ref "U1") (pin "64") (pinfunction "D2_64") (pintype "bidirectional"))
      (node (ref "U1") (pin "D2") (pinfunction "D2_D2") (pintype "bidirectional"))
    )
    (net (code "29") (name "HUM_SCK") (class "Default")
      (node (ref "IC2") (pin "3") (pinfunction "SCK_3") (pintype "input"))
      (node (ref "R14") (pin "1") (pinfunction "1_1") (pintype "passive"))
      (node (ref "U1") (pin "63") (pinfunction "D3_63") (pintype "bidirectional"))
      (node (ref "U1") (pin "99") (pinfunction "D3_99") (pintype "bidirectional"))
      (node (ref "U1") (pin "D3") (pinfunction "D3_D3") (pintype "bidirectional"))
    )
    (net (code "30") (name "I2C_SCL") (class "Default")
      (node (ref "JP14") (pin "2") (pinfunction "2_2") (pintype "passive"))
      (node (ref "JP17") (pin "2") (pinfunction "2_2") (pintype "passive"))
      (node (ref "R7") (pin "1") (pinfunction "1_1") (pintype "passive"))
      (node (ref "U1") (pin "101") (pinfunction "D1_101") (pintype "bidirectional"))
      (node (ref "U1") (pin "65") (pinfunction "D1_65") (pintype "bidirectional"))
      (node (ref "U1") (pin "D1") (pinfunction "D1_D1") (pintype "bidirectional"))
      (node (ref "U4") (pin "P3") (pinfunction "SCL_P3") (pintype "bidirectional"))
      (node (ref "U8") (pin "10") (pinfunction "SCL_10") (pintype "input"))
      (node (ref "U9") (pin "10") (pinfunction "SCL_10") (pintype "input"))
    )
    (net (code "31") (name "I2C_SDA") (class "Default")
      (node (ref "JP14") (pin "6") (pinfunction "6_6") (pintype "passive"))
      (node (ref "JP17") (pin "1") (pinfunction "1_1") (pintype "passive"))
      (node (ref "R6") (pin "1") (pinfunction "1_1") (pintype "passive"))
      (node (ref "U1") (pin "102") (pinfunction "D0_102") (pintype "bidirectional"))
      (node (ref "U1") (pin "66") (pinfunction "D0_66") (pintype "bidirectional"))
      (node (ref "U1") (pin "D0") (pinfunction "D0_D0") (pintype "bidirectional"))
      (node (ref "U4") (pin "P2") (pinfunction "SDA_P2") (pintype "bidirectional"))
      (node (ref "U8") (pin "9") (pinfunction "SDA_9") (pintype "bidirectional"))
      (node (ref "U9") (pin "9") (pinfunction "SDA_9") (pintype "bidirectional"))
    )
    (net (code "32") (name "Net-(IC1-EN)") (class "Default")
      (node (ref "C3") (pin "1") (pinfunction "1_1") (pintype "passive"))
      (node (ref "D1") (pin "C") (pinfunction "C_C") (pintype "passive"))
      (node (ref "IC1") (pin "1") (pinfunction "EN_1") (pintype "input"))
      (node (ref "IC1") (pin "2") (pinfunction "OUT_2") (pintype "passive"))
      (node (ref "L1") (pin "2") (pinfunction "2_2") (pintype "passive"))
      (node (ref "R1") (pin "2") (pinfunction "2_2") (pintype "passive"))
    )
    (net (code "33") (name "Net-(IC1-LX)") (class "Default")
      (node (ref "D1") (pin "A") (pinfunction "A_A") (pintype "passive"))
      (node (ref "IC1") (pin "5") (pinfunction "LX_5") (pintype "input"))
      (node (ref "L2") (pin "1") (pinfunction "1_1") (pintype "passive"))
    )
    (net (code "34") (name "Net-(LED1-PadC)") (class "Default")
      (node (ref "LED1") (pin "C") (pinfunction "C_C") (pintype "passive"))
      (node (ref "R8") (pin "1") (pinfunction "1_1") (pintype "passive"))
    )
    (net (code "35") (name "Net-(LED2-PadC)") (class "Default")
      (node (ref "LED2") (pin "C") (pinfunction "C_C") (pintype "passive"))
      (node (ref "R9") (pin "2") (pinfunction "2_2") (pintype "passive"))
    )
    (net (code "36") (name "Net-(Q1-D)") (class "Default")
      (node (ref "Q1") (pin "3") (pinfunction "D_3") (pintype "passive"))
      (node (ref "R5") (pin "2") (pinfunction "2_2") (pintype "passive"))
      (node (ref "U2") (pin "1") (pinfunction "VIO_1") (pintype "bidirectional"))
    )
    (net (code "37") (name "Net-(Q2-G)") (class "Default")
      (node (ref "Q2") (pin "1") (pinfunction "G_1") (pintype "passive"))
      (node (ref "R10") (pin "1") (pinfunction "1_1") (pintype "passive"))
      (node (ref "SW1") (pin "1") (pinfunction "1_1") (pintype "passive"))
    )
    (net (code "38") (name "Net-(U1-B0-Pad18)") (class "Default")
      (node (ref "U1") (pin "18") (pinfunction "B0_18") (pintype "bidirectional"))
      (node (ref "U1") (pin "54") (pinfunction "B0_54") (pintype "bidirectional"))
      (node (ref "U1") (pin "B0") (pinfunction "B0_B0") (pintype "bidirectional"))
    )
    (net (code "39") (name "Net-(U1-B1-Pad17)") (class "Default")
      (node (ref "U1") (pin "17") (pinfunction "B1_17") (pintype "bidirectional"))
      (node (ref "U1") (pin "53") (pinfunction "B1_53") (pintype "bidirectional"))
      (node (ref "U1") (pin "B1") (pinfunction "B1_B1") (pintype "bidirectional"))
    )
    (net (code "40") (name "Net-(U1-B2-Pad16)") (class "Default")
      (node (ref "U1") (pin "16") (pinfunction "B2_16") (pintype "bidirectional"))
      (node (ref "U1") (pin "52") (pinfunction "B2_52") (pintype "bidirectional"))
      (node (ref "U1") (pin "B2") (pinfunction "B2_B2") (pintype "bidirectional"))
    )
    (net (code "41") (name "Net-(U1-B3-Pad15)") (class "Default")
      (node (ref "U1") (pin "15") (pinfunction "B3_15") (pintype "bidirectional"))
      (node (ref "U1") (pin "51") (pinfunction "B3_51") (pintype "bidirectional"))
      (node (ref "U1") (pin "B3") (pinfunction "B3_B3") (pintype "bidirectional"))
    )
    (net (code "42") (name "Net-(U1-B4-Pad14)") (class "Default")
      (node (ref "U1") (pin "14") (pinfunction "B4_14") (pintype "bidirectional"))
      (node (ref "U1") (pin "50") (pinfunction "B4_50") (pintype "bidirectional"))
      (node (ref "U1") (pin "B4") (pinfunction "B4_B4") (pintype "bidirectional"))
    )
    (net (code "43") (name "Net-(U1-B5-Pad13)") (class "Default")
      (node (ref "U1") (pin "13") (pinfunction "B5_13") (pintype "bidirectional"))
      (node (ref "U1") (pin "49") (pinfunction "B5_49") (pintype "bidirectional"))
      (node (ref "U1") (pin "B5") (pinfunction "B5_B5") (pintype "bidirectional"))
    )
    (net (code "44") (name "Net-(U1-C0-Pad108)") (class "Default")
      (node (ref "U1") (pin "108") (pinfunction "C0_108") (pintype "bidirectional"))
      (node (ref "U1") (pin "72") (pinfunction "C0_72") (pintype "bidirectional"))
      (node (ref "U1") (pin "C0") (pinfunction "C0_C0") (pintype "bidirectional"))
    )
    (net (code "45") (name "Net-(U1-C1-Pad107)") (class "Default")
      (node (ref "U1") (pin "107") (pinfunction "C1_107") (pintype "bidirectional"))
      (node (ref "U1") (pin "71") (pinfunction "C1_71") (pintype "bidirectional"))
      (node (ref "U1") (pin "C1") (pinfunction "C1_C1") (pintype "bidirectional"))
    )
    (net (code "46") (name "Net-(U1-C2-Pad106)") (class "Default")
      (node (ref "U1") (pin "106") (pinfunction "C2_106") (pintype "bidirectional"))
      (node (ref "U1") (pin "70") (pinfunction "C2_70") (pintype "bidirectional"))
      (node (ref "U1") (pin "C2") (pinfunction "C2_C2") (pintype "bidirectional"))
    )
    (net (code "47") (name "Net-(U1-C3-Pad105)") (class "Default")
      (node (ref "U1") (pin "105") (pinfunction "C3_105") (pintype "bidirectional"))
      (node (ref "U1") (pin "69") (pinfunction "C3_69") (pintype "bidirectional"))
      (node (ref "U1") (pin "C3") (pinfunction "C3_C3") (pintype "bidirectional"))
    )
    (net (code "48") (name "Net-(U1-C4-Pad104)") (class "Default")
      (node (ref "U1") (pin "104") (pinfunction "C4_104") (pintype "bidirectional"))
      (node (ref "U1") (pin "68") (pinfunction "C4_68") (pintype "bidirectional"))
      (node (ref "U1") (pin "C4") (pinfunction "C4_C4") (pintype "bidirectional"))
    )
    (net (code "49") (name "Net-(U1-C5-Pad103)") (class "Default")
      (node (ref "U1") (pin "103") (pinfunction "C5_103") (pintype "bidirectional"))
      (node (ref "U1") (pin "67") (pinfunction "C5_67") (pintype "bidirectional"))
      (node (ref "U1") (pin "C5") (pinfunction "C5_C5") (pintype "bidirectional"))
    )
    (net (code "50") (name "Net-(U1-D7-Pad59)") (class "Default")
      (node (ref "U1") (pin "59") (pinfunction "D7_59") (pintype "bidirectional"))
      (node (ref "U1") (pin "95") (pinfunction "D7_95") (pintype "bidirectional"))
      (node (ref "U1") (pin "D7") (pinfunction "D7_D7") (pintype "bidirectional"))
    )
    (net (code "51") (name "Net-(U1-PadRST)") (class "Default")
      (node (ref "U1") (pin "56") (pinfunction "RST_56") (pintype "bidirectional"))
      (node (ref "U1") (pin "92") (pinfunction "RST_92") (pintype "bidirectional"))
      (node (ref "U1") (pin "RST") (pinfunction "RST_RST") (pintype "bidirectional"))
    )
    (net (code "52") (name "Net-(U2-OUT)") (class "Default")
      (node (ref "U2") (pin "3") (pinfunction "OUT_3") (pintype "bidirectional"))
      (node (ref "U5") (pin "6") (pinfunction "MCLK_6") (pintype "bidirectional"))
    )
    (net (code "53") (name "Net-(U3-PROG)") (class "Default")
      (node (ref "R11") (pin "2") (pinfunction "2_2") (pintype "passive"))
      (node (ref "U3") (pin "5") (pinfunction "PROG_5") (pintype "input"))
    )
    (net (code "54") (name "SDC_CD") (class "Default")
      (node (ref "U1") (pin "11") (pinfunction "A1_11") (pintype "bidirectional"))
      (node (ref "U1") (pin "47") (pinfunction "A1_47") (pintype "bidirectional"))
      (node (ref "U1") (pin "A1") (pinfunction "A1_A1") (pintype "bidirectional"))
      (node (ref "U6") (pin "CD1") (pinfunction "CARD_DETECT_CD1") (pintype "passive"))
    )
    (net (code "55") (name "SPI_BAR_SS") (class "Default")
      (node (ref "Q1") (pin "1") (pinfunction "G_1") (pintype "passive"))
      (node (ref "R4") (pin "1") (pinfunction "1_1") (pintype "passive"))
      (node (ref "U1") (pin "12") (pinfunction "A0_12") (pintype "bidirectional"))
      (node (ref "U1") (pin "48") (pinfunction "A0_48") (pintype "bidirectional"))
      (node (ref "U1") (pin "A0") (pinfunction "A0_A0") (pintype "bidirectional"))
    )
    (net (code "56") (name "SPI_FREE_SS") (class "Default")
      (node (ref "JP9") (pin "2") (pinfunction "2_2") (pintype "passive"))
      (node (ref "R2") (pin "1") (pinfunction "1_1") (pintype "passive"))
      (node (ref "U1") (pin "60") (pinfunction "D6_60") (pintype "bidirectional"))
      (node (ref "U1") (pin "96") (pinfunction "D6_96") (pintype "bidirectional"))
      (node (ref "U1") (pin "D6") (pinfunction "D6_D6") (pintype "bidirectional"))
    )
    (net (code "57") (name "SPI_MISO") (class "Default")
      (node (ref "JP9") (pin "3") (pinfunction "3_3") (pintype "passive"))
      (node (ref "U1") (pin "44") (pinfunction "A4_44") (pintype "bidirectional"))
      (node (ref "U1") (pin "8") (pinfunction "A4_8") (pintype "bidirectional"))
      (node (ref "U1") (pin "A4") (pinfunction "A4_A4") (pintype "bidirectional"))
      (node (ref "U5") (pin "8") (pinfunction "DOUT_8") (pintype "bidirectional"))
      (node (ref "U6") (pin "7") (pinfunction "DATA_OUT_7") (pintype "output"))
    )
    (net (code "58") (name "SPI_MOSI") (class "Default")
      (node (ref "JP9") (pin "4") (pinfunction "4_4") (pintype "passive"))
      (node (ref "U1") (pin "43") (pinfunction "A5_43") (pintype "bidirectional"))
      (node (ref "U1") (pin "7") (pinfunction "A5_7") (pintype "bidirectional"))
      (node (ref "U1") (pin "A5") (pinfunction "A5_A5") (pintype "bidirectional"))
      (node (ref "U5") (pin "7") (pinfunction "DIN_7") (pintype "bidirectional"))
      (node (ref "U6") (pin "3") (pinfunction "DATA_IN_3") (pintype "input"))
    )
    (net (code "59") (name "SPI_SCK") (class "Default")
      (node (ref "JP9") (pin "5") (pinfunction "5_5") (pintype "passive"))
      (node (ref "U1") (pin "45") (pinfunction "A3_45") (pintype "bidirectional"))
      (node (ref "U1") (pin "9") (pinfunction "A3_9") (pintype "bidirectional"))
      (node (ref "U1") (pin "A3") (pinfunction "A3_A3") (pintype "bidirectional"))
      (node (ref "U5") (pin "1") (pinfunction "SCLK_1") (pintype "bidirectional"))
      (node (ref "U6") (pin "5") (pinfunction "SCLK_5") (pintype "input"))
    )
    (net (code "60") (name "SPI_SDC_SS") (class "Default")
      (node (ref "R3") (pin "1") (pinfunction "1_1") (pintype "passive"))
      (node (ref "U1") (pin "10") (pinfunction "A2_10") (pintype "bidirectional"))
      (node (ref "U1") (pin "46") (pinfunction "A2_46") (pintype "bidirectional"))
      (node (ref "U1") (pin "A2") (pinfunction "A2_A2") (pintype "bidirectional"))
      (node (ref "U6") (pin "2") (pinfunction "CS_2") (pintype "input"))
    )
    (net (code "61") (name "VOC_AIN") (class "Default")
      (node (ref "JP13") (pin "7") (pinfunction "7_7") (pintype "passive"))
      (node (ref "JP14") (pin "1") (pinfunction "1_1") (pintype "passive"))
      (node (ref "U9") (pin "7") (pinfunction "AIN3_7") (pintype "input"))
    )
    (net (code "62") (name "unconnected-(IC1-NC-Pad3)") (class "Default")
      (node (ref "IC1") (pin "3") (pinfunction "NC_3") (pintype "input"))
    )
    (net (code "63") (name "unconnected-(U4-NC-PadP6)") (class "Default")
      (node (ref "U4") (pin "P6") (pinfunction "NC_P6") (pintype "no_connect"))
    )
    (net (code "64") (name "unconnected-(U5-NC(PEN)-Pad4)") (class "Default")
      (node (ref "U5") (pin "4") (pinfunction "NC(PEN)_4") (pintype "bidirectional"))
    )
    (net (code "65") (name "unconnected-(U5-NC(PV)-Pad3)") (class "Default")
      (node (ref "U5") (pin "3") (pinfunction "NC(PV)_3") (pintype "bidirectional"))
    )
    (net (code "66") (name "unconnected-(U6-CARD_DETECT1-PadCD2)") (class "Default")
      (node (ref "U6") (pin "CD2") (pinfunction "CARD_DETECT1_CD2") (pintype "passive"))
    )
    (net (code "67") (name "unconnected-(U6-DAT1-Pad8)") (class "Default")
      (node (ref "U6") (pin "8") (pinfunction "DAT1_8") (pintype "bidirectional"))
    )
    (net (code "68") (name "unconnected-(U6-DAT2-Pad1)") (class "Default")
      (node (ref "U6") (pin "1") (pinfunction "DAT2_1") (pintype "bidirectional"))
    )
    (net (code "69") (name "unconnected-(U7-PadNC1)") (class "Default")
      (node (ref "U7") (pin "NC1") (pinfunction "NC1_NC1") (pintype "bidirectional"))
    )
    (net (code "70") (name "unconnected-(U7-PadNC2)") (class "Default")
      (node (ref "U7") (pin "NC2") (pinfunction "NC2_NC2") (pintype "bidirectional"))
    )
    (net (code "71") (name "unconnected-(U7-PadNC3)") (class "Default")
      (node (ref "U7") (pin "NC3") (pinfunction "NC3_NC3") (pintype "bidirectional"))
    )
    (net (code "72") (name "unconnected-(U7-PadNV1)") (class "Default")
      (node (ref "U7") (pin "NV1") (pinfunction "NV1_NV1") (pintype "bidirectional"))
    )
    (net (code "73") (name "unconnected-(U7-PadNV2)") (class "Default")
      (node (ref "U7") (pin "NV2") (pinfunction "NV2_NV2") (pintype "bidirectional"))
    )
    (net (code "74") (name "unconnected-(U7-PadRESETB)") (class "Default")
      (node (ref "U7") (pin "RESETB") (pinfunction "RESETB_RESETB") (pintype "bidirectional"))
    )
    (net (code "75") (name "unconnected-(U7-PadUART_CTS)") (class "Default")
      (node (ref "U7") (pin "UART_CTS") (pinfunction "UART_CTS_UART_CTS") (pintype "bidirectional"))
    )
    (net (code "76") (name "unconnected-(U7-PadUART_RTS)") (class "Default")
      (node (ref "U7") (pin "UART_RTS") (pinfunction "UART_RTS_UART_RTS") (pintype "bidirectional"))
    )
  )
)
